# PWR_P5V0A.net
KiCad netlist of a schematic drawn in Altium Designer
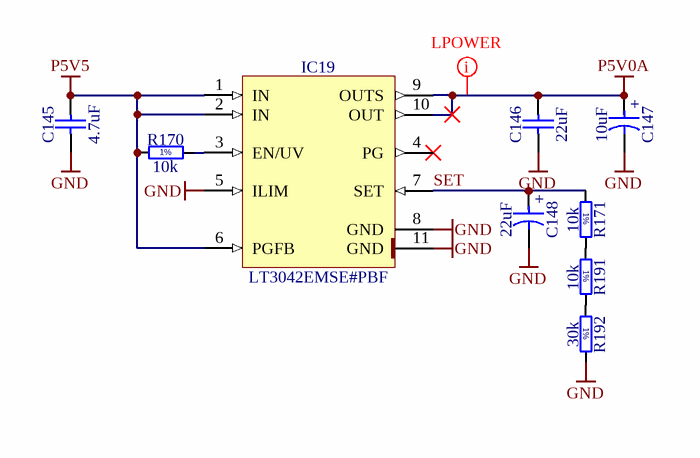
[diagram p0: PWR_P5V0A.SchDoc]

(export (version "E")
  (design (tool "Eeschema 10.0.6"))
  (components
    (comp (ref "C145")
      (value "4.7uF")
      (footprint "CAPC1709X95N")
      (description "Non-polarised capacitor")
      (fields
        (field (name "PART NUMBER") "CC0603_4.7UF_16V_10%_X5R")
        (field (name "VOLTAGE") "16V")
        (field (name "AUTHOR") "CERN DEM JLC")
      )
      (libsource (lib "Capacitors") (part "Capacitor - non polarized"))
    )
    (comp (ref "C146")
      (value "22uF")
      (footprint "CAPC2012X135N")
      (description "Non-polarised capacitor")
      (fields
        (field (name "PART NUMBER") "CC0805_22UF_16V_10%_X5R")
        (field (name "VOLTAGE") "16V")
        (field (name "AUTHOR") "CERN DEM JLC")
      )
      (libsource (lib "Capacitors") (part "Capacitor - non polarized"))
    )
    (comp (ref "C147")
      (value "10uF")
      (footprint "CAPMP3216X180N")
      (description "Polarised capacitor")
      (fields
        (field (name "PART NUMBER") "CTE3216-18_10UF_16V_20%_AVX_TCJ")
        (field (name "VOLTAGE") "16V")
        (field (name "AUTHOR") "CERN DEM JLC")
      )
      (libsource (lib "Capacitors") (part "Capacitor - polarized"))
    )
    (comp (ref "C148")
      (value "22uF")
      (footprint "CAPMP3216X180N")
      (description "Polarised capacitor")
      (fields
        (field (name "PART NUMBER") "CTE3216-18_22UF_10V_10%")
        (field (name "VOLTAGE") "10V")
        (field (name "AUTHOR") "CERN DEM JLC")
      )
      (libsource (lib "Capacitors") (part "Capacitor - polarized"))
    )
    (comp (ref "IC19")
      (value "LT3042EMSE#PBF")
      (footprint "SOP50P490X110-11N-R168X198")
      (description "20V, 200mA, Ultralow Noise, Ultrahigh PSRR RF Linear Regulator")
      (fields (field (name "MANUFACTURER") "LINEAR TECHNOLOGY") (field (name "AUTHOR") "CERN DEM MR"))
      (libsource (lib "ICs And Semiconductors") (part "LT3042"))
    )
    (comp (ref "R170")
      (value "10k")
      (footprint "RESC1005X40N")
      (description "Resistor - 1%")
      (fields
        (field (name "PART NUMBER") "R0402_10K_1%_0.0625W_100PPM")
        (field (name "POWER") "0.0625W")
        (field (name "AUTHOR") "CERN DEM JLC")
      )
      (libsource (lib "Resistors") (part "Resistor - 1%"))
    )
    (comp (ref "R171")
      (value "10k")
      (footprint "RESC1005X40N")
      (description "Resistor - 1%")
      (fields
        (field (name "PART NUMBER") "R0402_10K_1%_0.0625W_100PPM")
        (field (name "MANUFACTURER") "GENERIC")
        (field (name "AUTHOR") "CERN DEM JLC")
      )
      (libsource (lib "Resistors") (part "Resistor - 1%"))
    )
    (comp (ref "R191")
      (value "10k")
      (footprint "RESC1005X40N")
      (description "Resistor - 1%")
      (fields
        (field (name "PART NUMBER") "R0402_10K_1%_0.0625W_100PPM")
        (field (name "POWER") "0.0625W")
        (field (name "AUTHOR") "CERN DEM JLC")
      )
      (libsource (lib "Resistors") (part "Resistor - 1%"))
    )
    (comp (ref "R192")
      (value "30k")
      (footprint "RESC1005X40N")
      (description "Resistor - 1%")
      (fields
        (field (name "PART NUMBER") "R0402_30K_1%_0.0625W_100PPM")
        (field (name "POWER") "0.0625W")
        (field (name "AUTHOR") "CERN DEM JLC")
      )
      (libsource (lib "Resistors") (part "Resistor - 1%"))
    )
  )
  (nets
    (net (code "1") (name "/SET") (class "Default")
      (node (ref "C148") (pin "1") (pinfunction "1_1") (pintype "passive"))
      (node (ref "IC19") (pin "7") (pinfunction "SET_7") (pintype "input"))
      (node (ref "R171") (pin "1") (pinfunction "1_1") (pintype "passive"))
    )
    (net (code "2") (name "GND") (class "Default")
      (node (ref "C145") (pin "1") (pinfunction "1_1") (pintype "passive"))
      (node (ref "C146") (pin "1") (pinfunction "1_1") (pintype "passive"))
      (node (ref "C147") (pin "2") (pinfunction "2_2") (pintype "passive"))
      (node (ref "C148") (pin "2") (pinfunction "2_2") (pintype "passive"))
      (node (ref "IC19") (pin "11") (pinfunction "GND_11") (pintype "power_in"))
      (node (ref "IC19") (pin "5") (pinfunction "ILIM_5") (pintype "input"))
      (node (ref "IC19") (pin "8") (pinfunction "GND_8") (pintype "power_in"))
      (node (ref "R192") (pin "2") (pinfunction "2_2") (pintype "passive"))
    )
    (net (code "3") (name "Net-(IC19-EN{slash}UV)") (class "Default")
      (node (ref "IC19") (pin "3") (pinfunction "EN/UV_3") (pintype "input"))
      (node (ref "R170") (pin "2") (pinfunction "2_2") (pintype "passive"))
    )
    (net (code "4") (name "Net-(R171-Pad2)") (class "Default")
      (node (ref "R171") (pin "2") (pinfunction "2_2") (pintype "passive"))
      (node (ref "R191") (pin "1") (pinfunction "1_1") (pintype "passive"))
    )
    (net (code "5") (name "Net-(R191-Pad2)") (class "Default")
      (node (ref "R191") (pin "2") (pinfunction "2_2") (pintype "passive"))
      (node (ref "R192") (pin "1") (pinfunction "1_1") (pintype "passive"))
    )
    (net (code "6") (name "P5V0A") (class "Default")
      (node (ref "C146") (pin "2") (pinfunction "2_2") (pintype "passive"))
      (node (ref "C147") (pin "1") (pinfunction "1_1") (pintype "passive"))
      (node (ref "IC19") (pin "10") (pinfunction "OUT_10") (pintype "output"))
      (node (ref "IC19") (pin "9") (pinfunction "OUTS_9") (pintype "output"))
    )
    (net (code "7") (name "P5V5") (class "Default")
      (node (ref "C145") (pin "2") (pinfunction "2_2") (pintype "passive"))
      (node (ref "IC19") (pin "1") (pinfunction "IN_1") (pintype "input"))
      (node (ref "IC19") (pin "2") (pinfunction "IN_2") (pintype "input"))
      (node (ref "IC19") (pin "6") (pinfunction "PGFB_6") (pintype "input"))
      (node (ref "R170") (pin "1") (pinfunction "1_1") (pintype "passive"))
    )
    (net (code "8") (name "unconnected-(IC19-PG-Pad4)") (class "Default")
      (node (ref "IC19") (pin "4") (pinfunction "PG_4") (pintype "output+no_connect"))
    )
  )
)
